# Main.net
KiCad netlist of a schematic drawn in Altium Designer
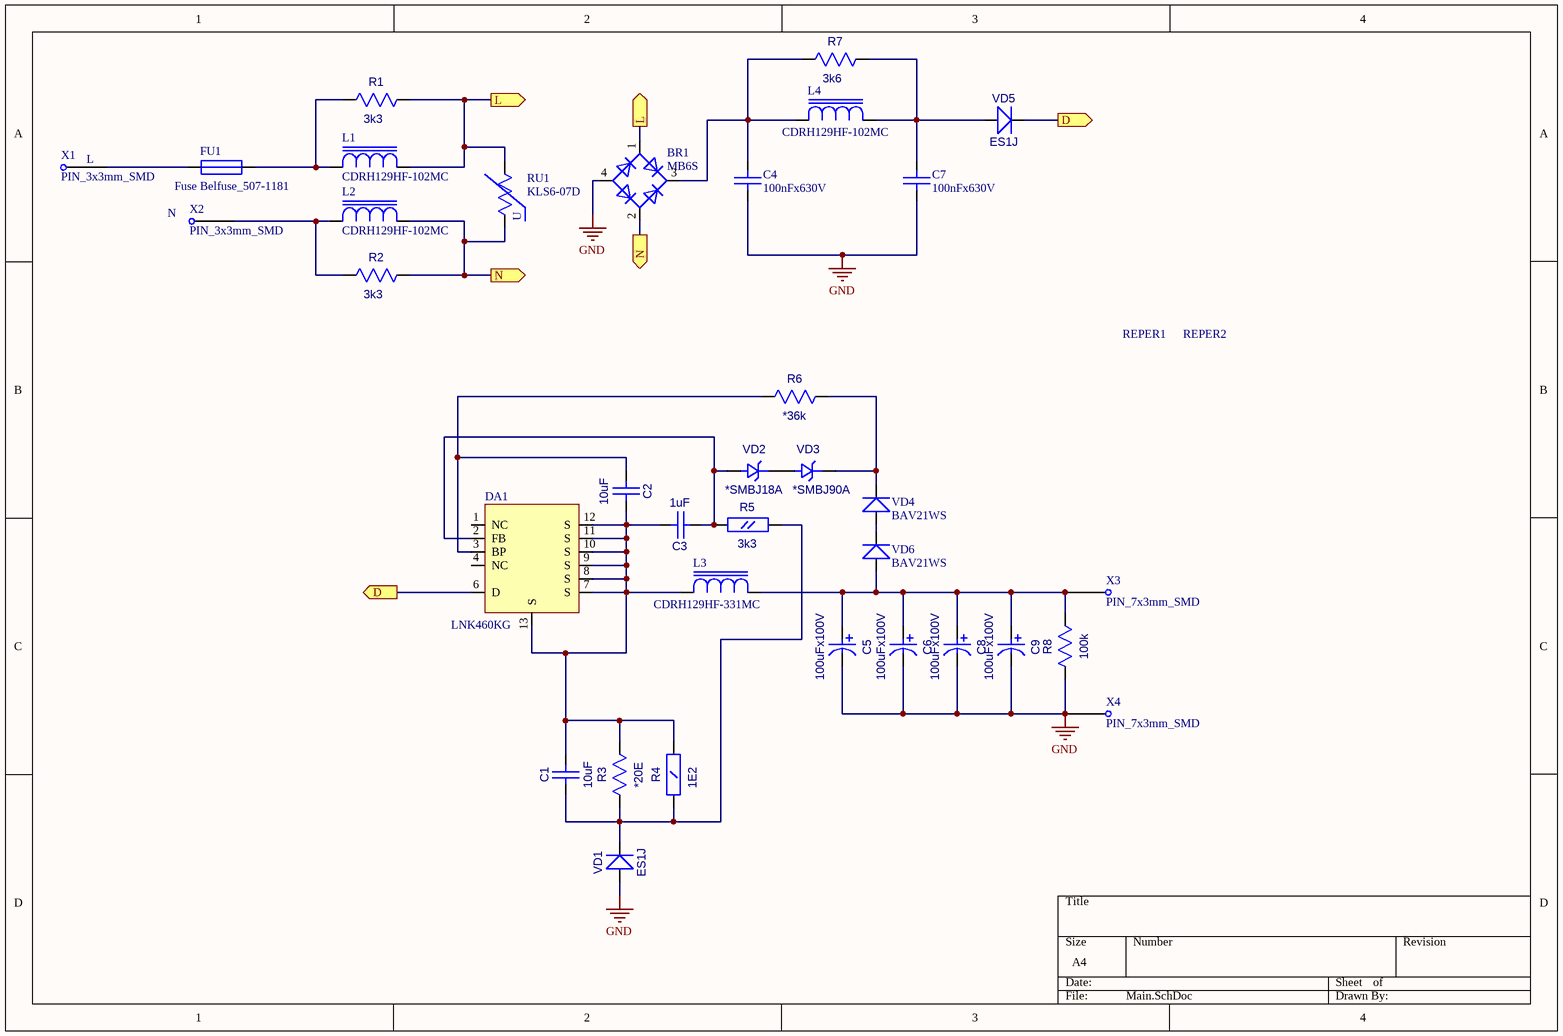
[diagram p0: Main.SchDoc]

(export (version "E")
  (design (tool "Eeschema 10.0.6"))
  (components
    (comp (ref "BR1") (value "MB6S") (footprint "TO-269AA") (libsource (lib "gprs_modem") (part "MB6S")))
    (comp (ref "C1")
      (value "10uF")
      (footprint "CC0805")
      (description "CC0805")
      (libsource (lib "gprs_modem_2") (part "CC0805"))
    )
    (comp (ref "C2")
      (value "10uF")
      (footprint "CC0805")
      (description "CC0805")
      (libsource (lib "gprs_modem_2") (part "CC0805"))
    )
    (comp (ref "C3")
      (value "1uF")
      (footprint "CC0805")
      (description "CC0805")
      (libsource (lib "gprs_modem_2") (part "CC0805"))
    )
    (comp (ref "C4")
      (value "100nFx630V")
      (footprint "CAP_630V_100NF")
      (libsource (lib "gprs_modem") (part "Cap_HV"))
    )
    (comp (ref "C5")
      (value "100uFx100V")
      (footprint "CAP_ELEC_10x21")
      (description "CAP0.5")
      (libsource (lib "shlagbaum") (part "CAP0.5"))
    )
    (comp (ref "C6")
      (value "100uFx100V")
      (footprint "CAP_ELEC_10x21")
      (description "CAP0.5")
      (libsource (lib "shlagbaum") (part "CAP0.5"))
    )
    (comp (ref "C7")
      (value "100nFx630V")
      (footprint "CAP_630V_100NF")
      (libsource (lib "gprs_modem") (part "Cap_HV"))
    )
    (comp (ref "C8")
      (value "100uFx100V")
      (footprint "CAP_ELEC_10x21")
      (description "CAP0.5")
      (libsource (lib "shlagbaum") (part "CAP0.5"))
    )
    (comp (ref "C9")
      (value "100uFx100V")
      (footprint "CAP_ELEC_10x21")
      (description "CAP0.5")
      (libsource (lib "shlagbaum") (part "CAP0.5"))
    )
    (comp (ref "DA1")
      (value "LNK460KG")
      (footprint "eSOP-12")
      (libsource (lib "gprs_modem") (part "LNK460KG"))
    )
    (comp (ref "FU1")
      (value "Fuse Belfuse_507-1181")
      (footprint "FUSE_BELLFUSE")
      (libsource (lib "gprs_modem") (part "Fuse Belfuse_507-1181"))
    )
    (comp (ref "L1")
      (value "CDRH129HF-102MC")
      (footprint "IND CDRH129")
      (libsource (lib "gprs_modem") (part "IND CDRH129HF"))
    )
    (comp (ref "L2")
      (value "CDRH129HF-102MC")
      (footprint "IND CDRH129")
      (libsource (lib "gprs_modem") (part "IND CDRH129HF"))
    )
    (comp (ref "L3")
      (value "CDRH129HF-331MC")
      (footprint "IND CDRH129")
      (libsource (lib "gprs_modem") (part "IND CDRH129HF"))
    )
    (comp (ref "L4")
      (value "CDRH129HF-102MC")
      (footprint "IND CDRH129")
      (libsource (lib "gprs_modem") (part "IND CDRH129HF"))
    )
    (comp (ref "R1")
      (value "3k3")
      (footprint "RC1206")
      (description "RC1206")
      (libsource (lib "gprs_modem") (part "RC1206"))
    )
    (comp (ref "R2")
      (value "3k3")
      (footprint "RC1206")
      (description "RC1206")
      (libsource (lib "gprs_modem") (part "RC1206"))
    )
    (comp (ref "R3")
      (value "*20E")
      (footprint "RC0805")
      (description "RC0805")
      (libsource (lib "gprs_modem") (part "RC0805"))
    )
    (comp (ref "R4")
      (value "1E2")
      (footprint "RC1206")
      (description "RC1206")
      (libsource (lib "gprs_modem_2") (part "RC1206"))
    )
    (comp (ref "R5")
      (value "3k3")
      (footprint "RC0805")
      (description "RC0805")
      (libsource (lib "gprs_modem_2") (part "RC0805"))
    )
    (comp (ref "R6")
      (value "*36k")
      (footprint "RC0603")
      (description "RC0603")
      (libsource (lib "gprs_modem") (part "RC0603"))
    )
    (comp (ref "R7")
      (value "3k6")
      (footprint "RC1206-2M")
      (description "RC1206")
      (libsource (lib "gprs_modem") (part "RC1206"))
    )
    (comp (ref "R8")
      (value "100k")
      (footprint "RC0805")
      (description "RC0805")
      (libsource (lib "shlagbaum") (part "RC0805"))
    )
    (comp (ref "REPER1")
      (value "REPER1.2")
      (footprint "REPER1.2")
      (libsource (lib "gprs_modem") (part "REPER1.2"))
    )
    (comp (ref "REPER2")
      (value "REPER1.2")
      (footprint "REPER1.2")
      (libsource (lib "gprs_modem") (part "REPER1.2"))
    )
    (comp (ref "RU1")
      (value "KLS6-07D")
      (footprint "Varistor_7mm")
      (libsource (lib "gprs_modem") (part "Varistor_KLS6-07D431K"))
    )
    (comp (ref "VD1")
      (value "ES1J")
      (footprint "SMA")
      (description "Schottky Rectifier")
      (libsource (lib "gprs_modem") (part "SS14"))
    )
    (comp (ref "VD2")
      (value "*SMBJ18A")
      (footprint "SMB")
      (description "SMBJ")
      (libsource (lib "gprs_modem") (part "SMBJ"))
    )
    (comp (ref "VD3")
      (value "*SMBJ90A")
      (footprint "SMB")
      (description "SMBJ")
      (libsource (lib "gprs_modem") (part "SMBJ"))
    )
    (comp (ref "VD4") (value "BAV21WS") (footprint "SOD-323") (libsource (lib "gprs_modem") (part "BAV21WS")))
    (comp (ref "VD5")
      (value "ES1J")
      (footprint "SMA")
      (description "Schottky Rectifier")
      (libsource (lib "gprs_modem") (part "SS14"))
    )
    (comp (ref "VD6") (value "BAV21WS") (footprint "SOD-323") (libsource (lib "gprs_modem") (part "BAV21WS")))
    (comp (ref "X1")
      (value "PIN_3x3mm_SMD")
      (footprint "PIN_3x3mm_SMD")
      (libsource (lib "gprs_modem_2") (part "PIN_3x3mm_SMD"))
    )
    (comp (ref "X2")
      (value "PIN_3x3mm_SMD")
      (footprint "PIN_3x3mm_SMD")
      (libsource (lib "gprs_modem_2") (part "PIN_3x3mm_SMD"))
    )
    (comp (ref "X3")
      (value "PIN_7x3mm_SMD")
      (footprint "PIN_7x3mm_SMD")
      (libsource (lib "gprs_modem") (part "PIN_7x3mm_SMD"))
    )
    (comp (ref "X4")
      (value "PIN_7x3mm_SMD")
      (footprint "PIN_7x3mm_SMD")
      (libsource (lib "gprs_modem") (part "PIN_7x3mm_SMD"))
    )
  )
  (nets
    (net (code "1") (name "/D") (class "Default")
      (node (ref "DA1") (pin "6") (pinfunction "D_6") (pintype "passive"))
      (node (ref "VD5") (pin "2") (pinfunction "K_2") (pintype "passive"))
    )
    (net (code "2") (name "/L") (class "Default")
      (node (ref "BR1") (pin "1") (pinfunction "C_1") (pintype "passive"))
      (node (ref "L1") (pin "2") (pinfunction "B_2") (pintype "passive"))
      (node (ref "R1") (pin "2") (pinfunction "B_2") (pintype "passive"))
      (node (ref "RU1") (pin "2") (pinfunction "B_2") (pintype "passive"))
    )
    (net (code "3") (name "/N") (class "Default")
      (node (ref "BR1") (pin "2") (pinfunction "C_2") (pintype "passive"))
      (node (ref "L2") (pin "2") (pinfunction "B_2") (pintype "passive"))
      (node (ref "R2") (pin "2") (pinfunction "B_2") (pintype "passive"))
      (node (ref "RU1") (pin "1") (pinfunction "A_1") (pintype "passive"))
    )
    (net (code "4") (name "GND") (class "Default")
      (node (ref "BR1") (pin "4") (pinfunction "4_4") (pintype "passive"))
      (node (ref "C4") (pin "2") (pinfunction "B_2") (pintype "passive"))
      (node (ref "C5") (pin "2") (pintype "passive"))
      (node (ref "C6") (pin "2") (pintype "passive"))
      (node (ref "C7") (pin "2") (pinfunction "B_2") (pintype "passive"))
      (node (ref "C8") (pin "2") (pintype "passive"))
      (node (ref "C9") (pin "2") (pintype "passive"))
      (node (ref "R8") (pin "1") (pinfunction "A_1") (pintype "passive"))
      (node (ref "VD1") (pin "1") (pinfunction "A_1") (pintype "passive"))
      (node (ref "X4") (pin "1") (pinfunction "1_1") (pintype "passive"))
    )
    (net (code "5") (name "Net-(BR1-K)") (class "Default")
      (node (ref "BR1") (pin "3") (pinfunction "K_3") (pintype "passive"))
      (node (ref "C4") (pin "1") (pinfunction "A_1") (pintype "passive"))
      (node (ref "L4") (pin "1") (pinfunction "A_1") (pintype "passive"))
      (node (ref "R7") (pin "1") (pinfunction "A_1") (pintype "passive"))
    )
    (net (code "6") (name "Net-(C1-A)") (class "Default")
      (node (ref "C1") (pin "1") (pinfunction "A_1") (pintype "passive"))
      (node (ref "R3") (pin "1") (pinfunction "A_1") (pintype "passive"))
      (node (ref "R4") (pin "1") (pinfunction "A_1") (pintype "passive"))
      (node (ref "R5") (pin "2") (pinfunction "B_2") (pintype "passive"))
      (node (ref "VD1") (pin "2") (pinfunction "K_2") (pintype "passive"))
    )
    (net (code "7") (name "Net-(C1-B)") (class "Default")
      (node (ref "C1") (pin "2") (pinfunction "B_2") (pintype "passive"))
      (node (ref "C2") (pin "2") (pinfunction "B_2") (pintype "passive"))
      (node (ref "C3") (pin "2") (pinfunction "B_2") (pintype "passive"))
      (node (ref "DA1") (pin "10") (pinfunction "S_10") (pintype "passive"))
      (node (ref "DA1") (pin "11") (pinfunction "S_11") (pintype "passive"))
      (node (ref "DA1") (pin "12") (pinfunction "S_12") (pintype "passive"))
      (node (ref "DA1") (pin "13") (pinfunction "S_13") (pintype "passive"))
      (node (ref "DA1") (pin "7") (pinfunction "S_7") (pintype "passive"))
      (node (ref "DA1") (pin "8") (pinfunction "S_8") (pintype "passive"))
      (node (ref "DA1") (pin "9") (pinfunction "S_9") (pintype "passive"))
      (node (ref "L3") (pin "1") (pinfunction "A_1") (pintype "passive"))
      (node (ref "R3") (pin "2") (pinfunction "B_2") (pintype "passive"))
      (node (ref "R4") (pin "2") (pinfunction "B_2") (pintype "passive"))
    )
    (net (code "8") (name "Net-(C2-A)") (class "Default")
      (node (ref "C2") (pin "1") (pinfunction "A_1") (pintype "passive"))
      (node (ref "DA1") (pin "3") (pinfunction "BP_3") (pintype "passive"))
      (node (ref "R6") (pin "1") (pinfunction "A_1") (pintype "passive"))
    )
    (net (code "9") (name "Net-(C3-A)") (class "Default")
      (node (ref "C3") (pin "1") (pinfunction "A_1") (pintype "passive"))
      (node (ref "DA1") (pin "2") (pinfunction "FB_2") (pintype "passive"))
      (node (ref "R5") (pin "1") (pinfunction "A_1") (pintype "passive"))
      (node (ref "VD2") (pin "1") (pinfunction "A_1") (pintype "passive"))
    )
    (net (code "10") (name "Net-(C7-A)") (class "Default")
      (node (ref "C7") (pin "1") (pinfunction "A_1") (pintype "passive"))
      (node (ref "L4") (pin "2") (pinfunction "B_2") (pintype "passive"))
      (node (ref "R7") (pin "2") (pinfunction "B_2") (pintype "passive"))
      (node (ref "VD5") (pin "1") (pinfunction "A_1") (pintype "passive"))
    )
    (net (code "11") (name "Net-(FU1-Pad1)") (class "Default")
      (node (ref "FU1") (pin "1") (pintype "passive"))
      (node (ref "X1") (pin "1") (pinfunction "1_1") (pintype "passive"))
    )
    (net (code "12") (name "Net-(L1-A)") (class "Default")
      (node (ref "FU1") (pin "2") (pintype "passive"))
      (node (ref "L1") (pin "1") (pinfunction "A_1") (pintype "passive"))
      (node (ref "R1") (pin "1") (pinfunction "A_1") (pintype "passive"))
    )
    (net (code "13") (name "Net-(L2-A)") (class "Default")
      (node (ref "L2") (pin "1") (pinfunction "A_1") (pintype "passive"))
      (node (ref "R2") (pin "1") (pinfunction "A_1") (pintype "passive"))
      (node (ref "X2") (pin "1") (pinfunction "1_1") (pintype "passive"))
    )
    (net (code "14") (name "Net-(L3-B)") (class "Default")
      (node (ref "C5") (pin "1") (pintype "passive"))
      (node (ref "C6") (pin "1") (pintype "passive"))
      (node (ref "C8") (pin "1") (pintype "passive"))
      (node (ref "C9") (pin "1") (pintype "passive"))
      (node (ref "L3") (pin "2") (pinfunction "B_2") (pintype "passive"))
      (node (ref "R8") (pin "2") (pinfunction "B_2") (pintype "passive"))
      (node (ref "VD6") (pin "1") (pinfunction "A_1") (pintype "passive"))
      (node (ref "X3") (pin "1") (pinfunction "1_1") (pintype "passive"))
    )
    (net (code "15") (name "Net-(R6-B)") (class "Default")
      (node (ref "R6") (pin "2") (pinfunction "B_2") (pintype "passive"))
      (node (ref "VD3") (pin "2") (pinfunction "K_2") (pintype "passive"))
      (node (ref "VD4") (pin "2") (pinfunction "K_2") (pintype "passive"))
    )
    (net (code "16") (name "Net-(VD2-K)") (class "Default")
      (node (ref "VD2") (pin "2") (pinfunction "K_2") (pintype "passive"))
      (node (ref "VD3") (pin "1") (pinfunction "A_1") (pintype "passive"))
    )
    (net (code "17") (name "Net-(VD4-A)") (class "Default")
      (node (ref "VD4") (pin "1") (pinfunction "A_1") (pintype "passive"))
      (node (ref "VD6") (pin "2") (pinfunction "K_2") (pintype "passive"))
    )
    (net (code "18") (name "unconnected-(DA1-NC-Pad1)") (class "Default")
      (node (ref "DA1") (pin "1") (pinfunction "NC_1") (pintype "passive"))
    )
    (net (code "19") (name "unconnected-(DA1-NC-Pad4)") (class "Default")
      (node (ref "DA1") (pin "4") (pinfunction "NC_4") (pintype "passive"))
    )
    (net (code "20") (name "unconnected-(REPER1-Pad1)") (class "Default")
      (node (ref "REPER1") (pin "1") (pintype "passive"))
    )
    (net (code "21") (name "unconnected-(REPER2-Pad1)") (class "Default")
      (node (ref "REPER2") (pin "1") (pintype "passive"))
    )
  )
)
